# EasyEDA_Schema_SourceFile.net
KiCad netlist of a schematic drawn in EasyEDA
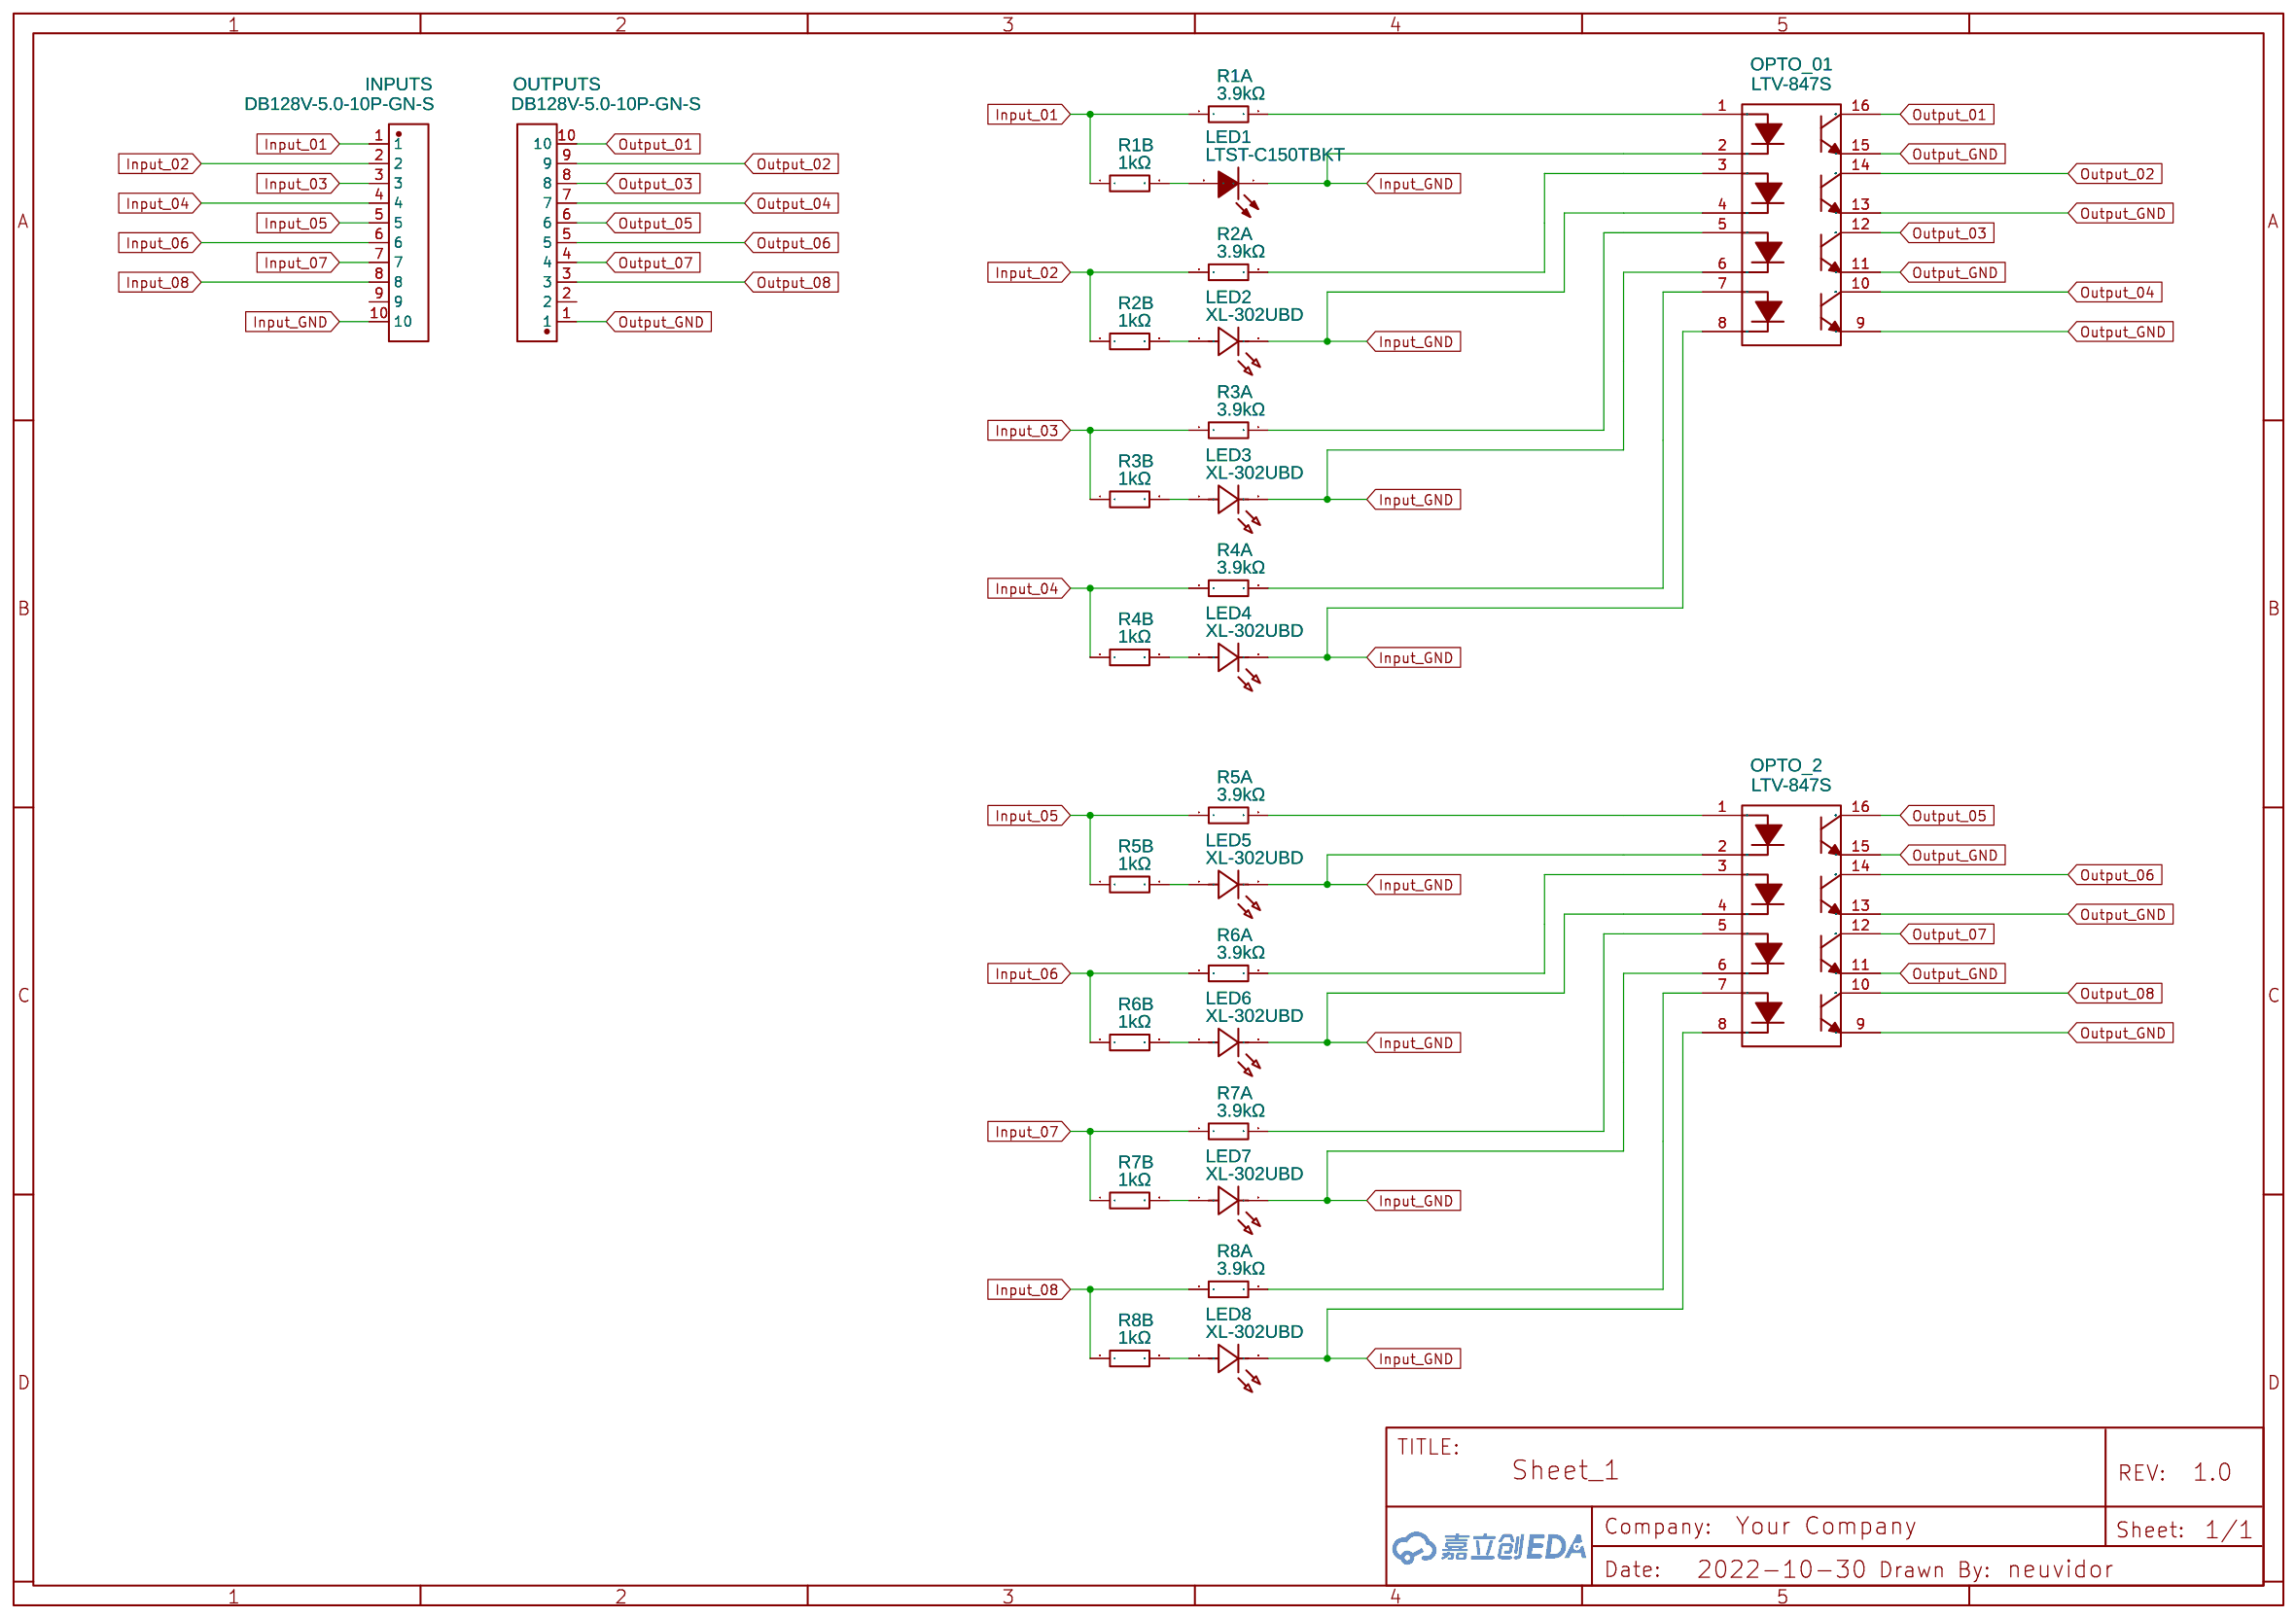
[diagram p0: schematic sheet]

(export (version "E")
  (design (tool "Eeschema 10.0.6"))
  (components
    (comp (ref "INPUTS")
      (value "DB128V-5.0-10P-GN-S")
      (fields (field (name "BOM_Supplier Part") "C725714"))
      (libsource (lib "") (part "DB128V-5.0-10P-GN-S"))
    )
    (comp (ref "LED1")
      (value "LTST-C150TBKT")
      (fields (field (name "BOM_Supplier Part") "C125088"))
      (libsource (lib "") (part "LTST-C150TBKT"))
    )
    (comp (ref "LED2")
      (value "XL-302UBD")
      (fields (field (name "BOM_Supplier Part") "C2895474"))
      (libsource (lib "") (part "XL-302UBD"))
    )
    (comp (ref "LED3")
      (value "XL-302UBD")
      (fields (field (name "BOM_Supplier Part") "C2895474"))
      (libsource (lib "") (part "XL-302UBD"))
    )
    (comp (ref "LED4")
      (value "XL-302UBD")
      (fields (field (name "BOM_Supplier Part") "C2895474"))
      (libsource (lib "") (part "XL-302UBD"))
    )
    (comp (ref "LED5")
      (value "XL-302UBD")
      (fields (field (name "BOM_Supplier Part") "C2895474"))
      (libsource (lib "") (part "XL-302UBD"))
    )
    (comp (ref "LED6")
      (value "XL-302UBD")
      (fields (field (name "BOM_Supplier Part") "C2895474"))
      (libsource (lib "") (part "XL-302UBD"))
    )
    (comp (ref "LED7")
      (value "XL-302UBD")
      (fields (field (name "BOM_Supplier Part") "C2895474"))
      (libsource (lib "") (part "XL-302UBD"))
    )
    (comp (ref "LED8")
      (value "XL-302UBD")
      (fields (field (name "BOM_Supplier Part") "C2895474"))
      (libsource (lib "") (part "XL-302UBD"))
    )
    (comp (ref "OPTO_01")
      (value "LTV-847S")
      (fields (field (name "BOM_Supplier Part") "C114599"))
      (libsource (lib "") (part "LTV-847S"))
    )
    (comp (ref "OPTO_2")
      (value "LTV-847S")
      (fields (field (name "BOM_Supplier Part") "C114599"))
      (libsource (lib "") (part "LTV-847S"))
    )
    (comp (ref "OUTPUTS")
      (value "DB128V-5.0-10P-GN-S")
      (fields (field (name "BOM_Supplier Part") "C725714"))
      (libsource (lib "") (part "DB128V-5.0-10P-GN-S_1"))
    )
    (comp (ref "R1A")
      (value "3.9kΩ")
      (fields
        (field (name "BOM_Manufacturer Part") "AECR1206F3K90K9")
        (field (name "BOM_Supplier Part") "C352079")
      )
      (libsource (lib "") (part "AECR1206F3K90K9_4"))
    )
    (comp (ref "R1B")
      (value "1kΩ")
      (fields
        (field (name "BOM_Manufacturer Part") "PTFR1206B1K00P9")
        (field (name "BOM_Supplier Part") "C351483")
      )
      (libsource (lib "") (part "PTFR1206B1K00P9_2"))
    )
    (comp (ref "R2A")
      (value "3.9kΩ")
      (fields
        (field (name "BOM_Manufacturer Part") "AECR1206F3K90K9")
        (field (name "BOM_Supplier Part") "C352079")
      )
      (libsource (lib "") (part "AECR1206F3K90K9_2"))
    )
    (comp (ref "R2B")
      (value "1kΩ")
      (fields
        (field (name "BOM_Manufacturer Part") "PTFR1206B1K00P9")
        (field (name "BOM_Supplier Part") "C351483")
      )
      (libsource (lib "") (part "PTFR1206B1K00P9"))
    )
    (comp (ref "R3A")
      (value "3.9kΩ")
      (fields
        (field (name "BOM_Manufacturer Part") "AECR1206F3K90K9")
        (field (name "BOM_Supplier Part") "C352079")
      )
      (libsource (lib "") (part "AECR1206F3K90K9_6"))
    )
    (comp (ref "R3B")
      (value "1kΩ")
      (fields
        (field (name "BOM_Manufacturer Part") "PTFR1206B1K00P9")
        (field (name "BOM_Supplier Part") "C351483")
      )
      (libsource (lib "") (part "PTFR1206B1K00P9_4"))
    )
    (comp (ref "R4A")
      (value "3.9kΩ")
      (fields
        (field (name "BOM_Manufacturer Part") "AECR1206F3K90K9")
        (field (name "BOM_Supplier Part") "C352079")
      )
      (libsource (lib "") (part "AECR1206F3K90K9_3"))
    )
    (comp (ref "R4B")
      (value "1kΩ")
      (fields
        (field (name "BOM_Manufacturer Part") "PTFR1206B1K00P9")
        (field (name "BOM_Supplier Part") "C351483")
      )
      (libsource (lib "") (part "PTFR1206B1K00P9_7"))
    )
    (comp (ref "R5A")
      (value "3.9kΩ")
      (fields
        (field (name "BOM_Manufacturer Part") "AECR1206F3K90K9")
        (field (name "BOM_Supplier Part") "C352079")
      )
      (libsource (lib "") (part "AECR1206F3K90K9_7"))
    )
    (comp (ref "R5B")
      (value "1kΩ")
      (fields
        (field (name "BOM_Manufacturer Part") "PTFR1206B1K00P9")
        (field (name "BOM_Supplier Part") "C351483")
      )
      (libsource (lib "") (part "PTFR1206B1K00P9_3"))
    )
    (comp (ref "R6A")
      (value "3.9kΩ")
      (fields
        (field (name "BOM_Manufacturer Part") "AECR1206F3K90K9")
        (field (name "BOM_Supplier Part") "C352079")
      )
      (libsource (lib "") (part "AECR1206F3K90K9"))
    )
    (comp (ref "R6B")
      (value "1kΩ")
      (fields
        (field (name "BOM_Manufacturer Part") "PTFR1206B1K00P9")
        (field (name "BOM_Supplier Part") "C351483")
      )
      (libsource (lib "") (part "PTFR1206B1K00P9_5"))
    )
    (comp (ref "R7A")
      (value "3.9kΩ")
      (fields
        (field (name "BOM_Manufacturer Part") "AECR1206F3K90K9")
        (field (name "BOM_Supplier Part") "C352079")
      )
      (libsource (lib "") (part "AECR1206F3K90K9_5"))
    )
    (comp (ref "R7B")
      (value "1kΩ")
      (fields
        (field (name "BOM_Manufacturer Part") "PTFR1206B1K00P9")
        (field (name "BOM_Supplier Part") "C351483")
      )
      (libsource (lib "") (part "PTFR1206B1K00P9_1"))
    )
    (comp (ref "R8A")
      (value "3.9kΩ")
      (fields
        (field (name "BOM_Manufacturer Part") "AECR1206F3K90K9")
        (field (name "BOM_Supplier Part") "C352079")
      )
      (libsource (lib "") (part "AECR1206F3K90K9_1"))
    )
    (comp (ref "R8B")
      (value "1kΩ")
      (fields
        (field (name "BOM_Manufacturer Part") "PTFR1206B1K00P9")
        (field (name "BOM_Supplier Part") "C351483")
      )
      (libsource (lib "") (part "PTFR1206B1K00P9_6"))
    )
  )
  (nets
    (net (code "1") (name "Input_01") (class "Default")
      (node (ref "INPUTS") (pin "1") (pinfunction "1_1") (pintype "unspecified"))
      (node (ref "R1A") (pin "1") (pinfunction "1_1") (pintype "unspecified"))
      (node (ref "R1B") (pin "1") (pinfunction "1_1") (pintype "unspecified"))
    )
    (net (code "2") (name "Input_02") (class "Default")
      (node (ref "INPUTS") (pin "2") (pinfunction "2_2") (pintype "unspecified"))
      (node (ref "R2A") (pin "1") (pinfunction "1_1") (pintype "unspecified"))
      (node (ref "R2B") (pin "1") (pinfunction "1_1") (pintype "unspecified"))
    )
    (net (code "3") (name "Input_03") (class "Default")
      (node (ref "INPUTS") (pin "3") (pinfunction "3_3") (pintype "unspecified"))
      (node (ref "R3A") (pin "1") (pinfunction "1_1") (pintype "unspecified"))
      (node (ref "R3B") (pin "1") (pinfunction "1_1") (pintype "unspecified"))
    )
    (net (code "4") (name "Input_04") (class "Default")
      (node (ref "INPUTS") (pin "4") (pinfunction "4_4") (pintype "unspecified"))
      (node (ref "R4A") (pin "1") (pinfunction "1_1") (pintype "unspecified"))
      (node (ref "R4B") (pin "1") (pinfunction "1_1") (pintype "unspecified"))
    )
    (net (code "5") (name "Input_05") (class "Default")
      (node (ref "INPUTS") (pin "5") (pinfunction "5_5") (pintype "unspecified"))
      (node (ref "R5A") (pin "1") (pinfunction "1_1") (pintype "unspecified"))
      (node (ref "R5B") (pin "1") (pinfunction "1_1") (pintype "unspecified"))
    )
    (net (code "6") (name "Input_06") (class "Default")
      (node (ref "INPUTS") (pin "6") (pinfunction "6_6") (pintype "unspecified"))
      (node (ref "R6A") (pin "1") (pinfunction "1_1") (pintype "unspecified"))
      (node (ref "R6B") (pin "1") (pinfunction "1_1") (pintype "unspecified"))
    )
    (net (code "7") (name "Input_07") (class "Default")
      (node (ref "INPUTS") (pin "7") (pinfunction "7_7") (pintype "unspecified"))
      (node (ref "R7A") (pin "1") (pinfunction "1_1") (pintype "unspecified"))
      (node (ref "R7B") (pin "1") (pinfunction "1_1") (pintype "unspecified"))
    )
    (net (code "8") (name "Input_08") (class "Default")
      (node (ref "INPUTS") (pin "8") (pinfunction "8_8") (pintype "unspecified"))
      (node (ref "R8A") (pin "1") (pinfunction "1_1") (pintype "unspecified"))
      (node (ref "R8B") (pin "1") (pinfunction "1_1") (pintype "unspecified"))
    )
    (net (code "9") (name "Input_GND") (class "Default")
      (node (ref "INPUTS") (pin "10") (pinfunction "10_10") (pintype "unspecified"))
      (node (ref "LED1") (pin "1") (pinfunction "K_1") (pintype "unspecified"))
      (node (ref "LED2") (pin "2") (pinfunction "A_2") (pintype "unspecified"))
      (node (ref "LED3") (pin "2") (pinfunction "A_2") (pintype "unspecified"))
      (node (ref "LED4") (pin "2") (pinfunction "A_2") (pintype "unspecified"))
      (node (ref "LED5") (pin "2") (pinfunction "A_2") (pintype "unspecified"))
      (node (ref "LED6") (pin "2") (pinfunction "A_2") (pintype "unspecified"))
      (node (ref "LED7") (pin "2") (pinfunction "A_2") (pintype "unspecified"))
      (node (ref "LED8") (pin "2") (pinfunction "A_2") (pintype "unspecified"))
      (node (ref "OPTO_01") (pin "2") (pinfunction "CAT1_2") (pintype "unspecified"))
      (node (ref "OPTO_01") (pin "4") (pinfunction "CAT2_4") (pintype "unspecified"))
      (node (ref "OPTO_01") (pin "6") (pinfunction "CAT3_6") (pintype "unspecified"))
      (node (ref "OPTO_01") (pin "8") (pinfunction "CAT4_8") (pintype "unspecified"))
      (node (ref "OPTO_2") (pin "2") (pinfunction "CAT1_2") (pintype "unspecified"))
      (node (ref "OPTO_2") (pin "4") (pinfunction "CAT2_4") (pintype "unspecified"))
      (node (ref "OPTO_2") (pin "6") (pinfunction "CAT3_6") (pintype "unspecified"))
      (node (ref "OPTO_2") (pin "8") (pinfunction "CAT4_8") (pintype "unspecified"))
    )
    (net (code "10") (name "Net-(LED1-A)") (class "Default")
      (node (ref "LED1") (pin "2") (pinfunction "A_2") (pintype "unspecified"))
      (node (ref "R1B") (pin "2") (pinfunction "2_2") (pintype "unspecified"))
    )
    (net (code "11") (name "Net-(LED2-K)") (class "Default")
      (node (ref "LED2") (pin "1") (pinfunction "K_1") (pintype "unspecified"))
      (node (ref "R2B") (pin "2") (pinfunction "2_2") (pintype "unspecified"))
    )
    (net (code "12") (name "Net-(LED3-K)") (class "Default")
      (node (ref "LED3") (pin "1") (pinfunction "K_1") (pintype "unspecified"))
      (node (ref "R3B") (pin "2") (pinfunction "2_2") (pintype "unspecified"))
    )
    (net (code "13") (name "Net-(LED4-K)") (class "Default")
      (node (ref "LED4") (pin "1") (pinfunction "K_1") (pintype "unspecified"))
      (node (ref "R4B") (pin "2") (pinfunction "2_2") (pintype "unspecified"))
    )
    (net (code "14") (name "Net-(LED5-K)") (class "Default")
      (node (ref "LED5") (pin "1") (pinfunction "K_1") (pintype "unspecified"))
      (node (ref "R5B") (pin "2") (pinfunction "2_2") (pintype "unspecified"))
    )
    (net (code "15") (name "Net-(LED6-K)") (class "Default")
      (node (ref "LED6") (pin "1") (pinfunction "K_1") (pintype "unspecified"))
      (node (ref "R6B") (pin "2") (pinfunction "2_2") (pintype "unspecified"))
    )
    (net (code "16") (name "Net-(LED7-K)") (class "Default")
      (node (ref "LED7") (pin "1") (pinfunction "K_1") (pintype "unspecified"))
      (node (ref "R7B") (pin "2") (pinfunction "2_2") (pintype "unspecified"))
    )
    (net (code "17") (name "Net-(LED8-K)") (class "Default")
      (node (ref "LED8") (pin "1") (pinfunction "K_1") (pintype "unspecified"))
      (node (ref "R8B") (pin "2") (pinfunction "2_2") (pintype "unspecified"))
    )
    (net (code "18") (name "Net-(OPTO_01-AN1)") (class "Default")
      (node (ref "OPTO_01") (pin "1") (pinfunction "AN1_1") (pintype "unspecified"))
      (node (ref "R1A") (pin "2") (pinfunction "2_2") (pintype "unspecified"))
    )
    (net (code "19") (name "Net-(OPTO_01-AN2)") (class "Default")
      (node (ref "OPTO_01") (pin "3") (pinfunction "AN2_3") (pintype "unspecified"))
      (node (ref "R2A") (pin "2") (pinfunction "2_2") (pintype "unspecified"))
    )
    (net (code "20") (name "Net-(OPTO_01-AN3)") (class "Default")
      (node (ref "OPTO_01") (pin "5") (pinfunction "AN3_5") (pintype "unspecified"))
      (node (ref "R3A") (pin "2") (pinfunction "2_2") (pintype "unspecified"))
    )
    (net (code "21") (name "Net-(OPTO_01-AN4)") (class "Default")
      (node (ref "OPTO_01") (pin "7") (pinfunction "AN4_7") (pintype "unspecified"))
      (node (ref "R4A") (pin "2") (pinfunction "2_2") (pintype "unspecified"))
    )
    (net (code "22") (name "Net-(OPTO_2-AN1)") (class "Default")
      (node (ref "OPTO_2") (pin "1") (pinfunction "AN1_1") (pintype "unspecified"))
      (node (ref "R5A") (pin "2") (pinfunction "2_2") (pintype "unspecified"))
    )
    (net (code "23") (name "Net-(OPTO_2-AN2)") (class "Default")
      (node (ref "OPTO_2") (pin "3") (pinfunction "AN2_3") (pintype "unspecified"))
      (node (ref "R6A") (pin "2") (pinfunction "2_2") (pintype "unspecified"))
    )
    (net (code "24") (name "Net-(OPTO_2-AN3)") (class "Default")
      (node (ref "OPTO_2") (pin "5") (pinfunction "AN3_5") (pintype "unspecified"))
      (node (ref "R7A") (pin "2") (pinfunction "2_2") (pintype "unspecified"))
    )
    (net (code "25") (name "Net-(OPTO_2-AN4)") (class "Default")
      (node (ref "OPTO_2") (pin "7") (pinfunction "AN4_7") (pintype "unspecified"))
      (node (ref "R8A") (pin "2") (pinfunction "2_2") (pintype "unspecified"))
    )
    (net (code "26") (name "Output_01") (class "Default")
      (node (ref "OPTO_01") (pin "16") (pinfunction "COL1_16") (pintype "unspecified"))
      (node (ref "OUTPUTS") (pin "10") (pinfunction "10_10") (pintype "unspecified"))
    )
    (net (code "27") (name "Output_02") (class "Default")
      (node (ref "OPTO_01") (pin "14") (pinfunction "COL2_14") (pintype "unspecified"))
      (node (ref "OUTPUTS") (pin "9") (pinfunction "9_9") (pintype "unspecified"))
    )
    (net (code "28") (name "Output_03") (class "Default")
      (node (ref "OPTO_01") (pin "12") (pinfunction "COL3_12") (pintype "unspecified"))
      (node (ref "OUTPUTS") (pin "8") (pinfunction "8_8") (pintype "unspecified"))
    )
    (net (code "29") (name "Output_04") (class "Default")
      (node (ref "OPTO_01") (pin "10") (pinfunction "COL4_10") (pintype "unspecified"))
      (node (ref "OUTPUTS") (pin "7") (pinfunction "7_7") (pintype "unspecified"))
    )
    (net (code "30") (name "Output_05") (class "Default")
      (node (ref "OPTO_2") (pin "16") (pinfunction "COL1_16") (pintype "unspecified"))
      (node (ref "OUTPUTS") (pin "6") (pinfunction "6_6") (pintype "unspecified"))
    )
    (net (code "31") (name "Output_06") (class "Default")
      (node (ref "OPTO_2") (pin "14") (pinfunction "COL2_14") (pintype "unspecified"))
      (node (ref "OUTPUTS") (pin "5") (pinfunction "5_5") (pintype "unspecified"))
    )
    (net (code "32") (name "Output_07") (class "Default")
      (node (ref "OPTO_2") (pin "12") (pinfunction "COL3_12") (pintype "unspecified"))
      (node (ref "OUTPUTS") (pin "4") (pinfunction "4_4") (pintype "unspecified"))
    )
    (net (code "33") (name "Output_08") (class "Default")
      (node (ref "OPTO_2") (pin "10") (pinfunction "COL4_10") (pintype "unspecified"))
      (node (ref "OUTPUTS") (pin "3") (pinfunction "3_3") (pintype "unspecified"))
    )
    (net (code "34") (name "Output_GND") (class "Default")
      (node (ref "OPTO_01") (pin "11") (pinfunction "EM3_11") (pintype "unspecified"))
      (node (ref "OPTO_01") (pin "13") (pinfunction "EM2_13") (pintype "unspecified"))
      (node (ref "OPTO_01") (pin "15") (pinfunction "EM1_15") (pintype "unspecified"))
      (node (ref "OPTO_01") (pin "9") (pinfunction "EM4_9") (pintype "unspecified"))
      (node (ref "OPTO_2") (pin "11") (pinfunction "EM3_11") (pintype "unspecified"))
      (node (ref "OPTO_2") (pin "13") (pinfunction "EM2_13") (pintype "unspecified"))
      (node (ref "OPTO_2") (pin "15") (pinfunction "EM1_15") (pintype "unspecified"))
      (node (ref "OPTO_2") (pin "9") (pinfunction "EM4_9") (pintype "unspecified"))
      (node (ref "OUTPUTS") (pin "1") (pinfunction "1_1") (pintype "unspecified"))
    )
    (net (code "35") (name "unconnected-(INPUTS-Pad9)") (class "Default")
      (node (ref "INPUTS") (pin "9") (pinfunction "9_9") (pintype "unspecified"))
    )
    (net (code "36") (name "unconnected-(OUTPUTS-Pad2)") (class "Default")
      (node (ref "OUTPUTS") (pin "2") (pinfunction "2_2") (pintype "unspecified"))
    )
  )
)
